# dlp_vco_dualosc_v1_1_pnl.net
KiCad netlist of a schematic drawn in EAGLE
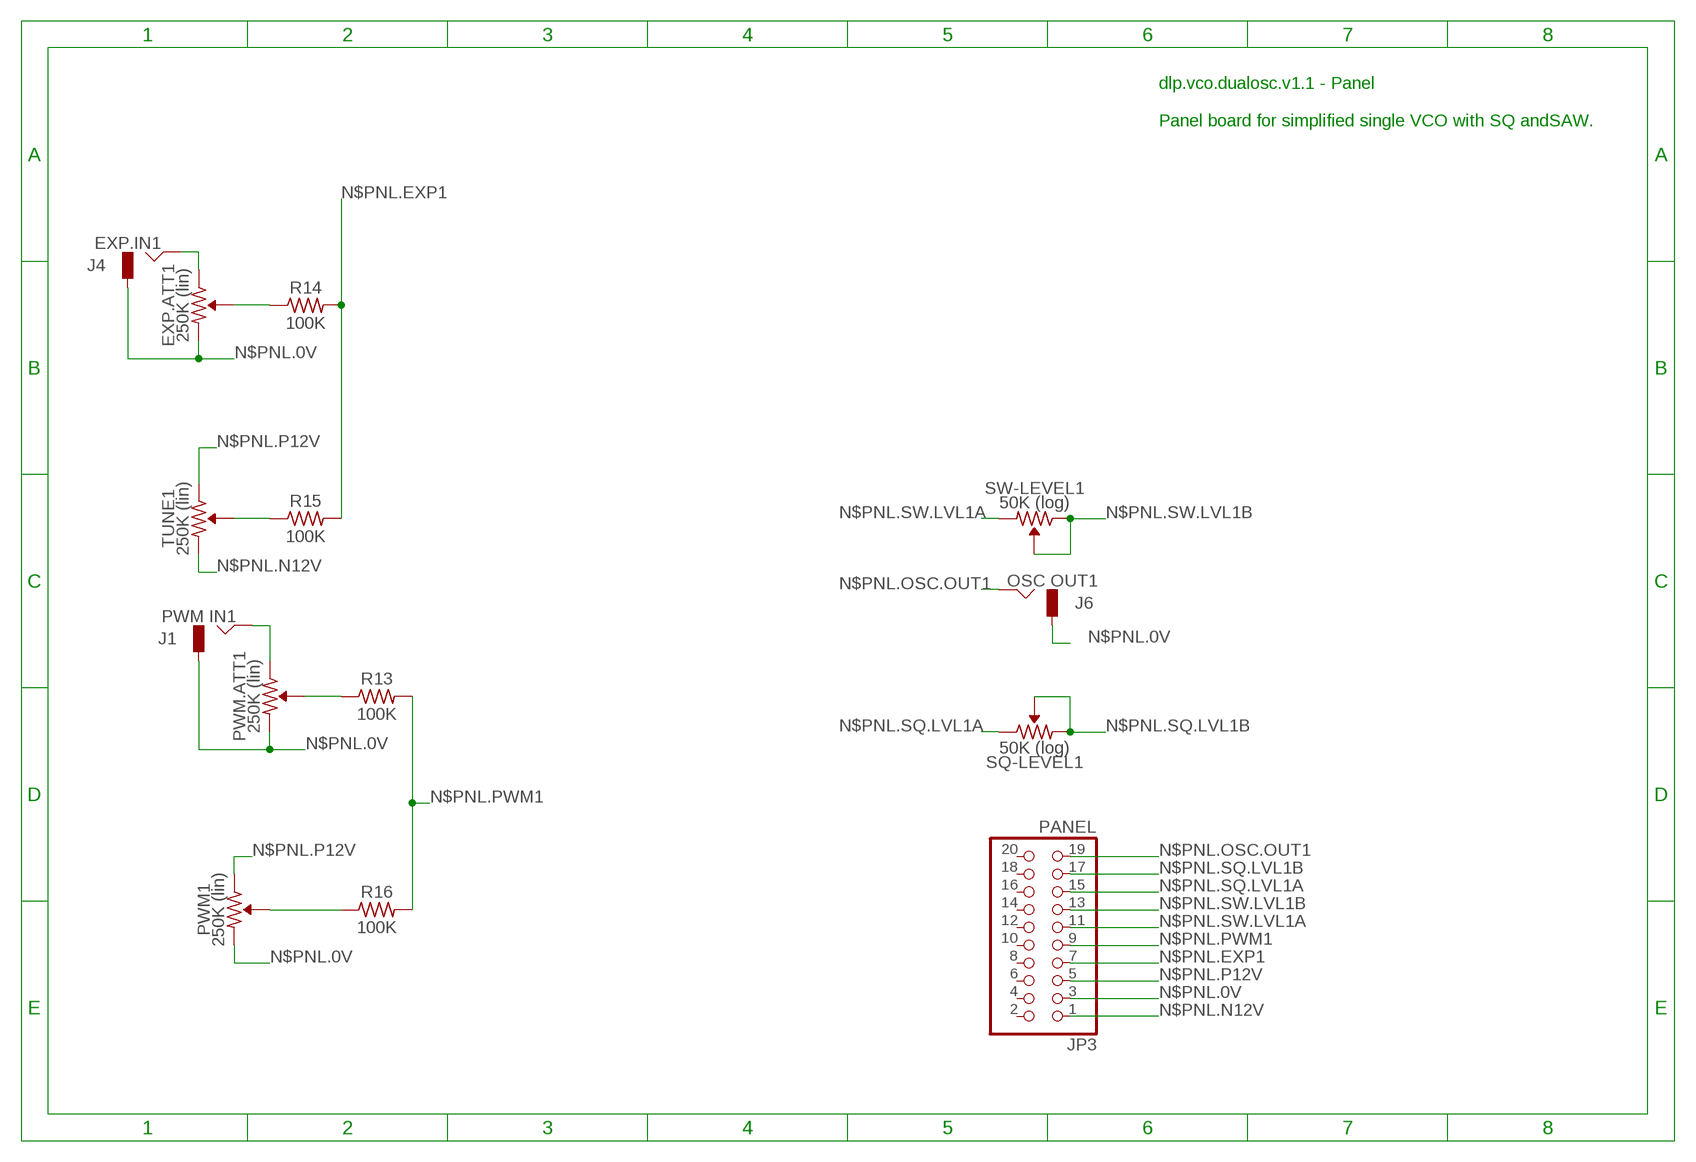
[diagram p0: schematic, sheet 1]

(export (version "E")
  (design (tool "Eeschema 10.0.6"))
  (components
    (comp (ref "EXP.ATT1")
      (value "250K (lin)")
      (footprint "eagle-import:R-VAR")
      (libsource (lib "eagle-import") (part "R-VAR"))
    )
    (comp (ref "J1")
      (value "PWM IN1")
      (footprint "eagle-import:JACK-M")
      (libsource (lib "eagle-import") (part "JACK-M"))
    )
    (comp (ref "J4")
      (value "EXP.IN1")
      (footprint "eagle-import:JACK-M")
      (libsource (lib "eagle-import") (part "JACK-M"))
    )
    (comp (ref "J6")
      (value "OSC OUT1")
      (footprint "eagle-import:JACK-M")
      (libsource (lib "eagle-import") (part "JACK-M"))
    )
    (comp (ref "JP3")
      (value "PANEL")
      (footprint "eagle-import:2X10")
      (libsource (lib "eagle-import") (part "PINHD-2X10"))
    )
    (comp (ref "PWM.ATT1")
      (value "250K (lin)")
      (footprint "eagle-import:R-VAR")
      (libsource (lib "eagle-import") (part "R-VAR"))
    )
    (comp (ref "PWM1")
      (value "250K (lin)")
      (footprint "eagle-import:R-VAR")
      (libsource (lib "eagle-import") (part "R-VAR"))
    )
    (comp (ref "R13")
      (value "100K")
      (footprint "eagle-import:0309_10")
      (libsource (lib "eagle-import") (part "R0309/10"))
    )
    (comp (ref "R14")
      (value "100K")
      (footprint "eagle-import:0309_10")
      (libsource (lib "eagle-import") (part "R0309/10"))
    )
    (comp (ref "R15")
      (value "100K")
      (footprint "eagle-import:0309_10")
      (libsource (lib "eagle-import") (part "R0309/10"))
    )
    (comp (ref "R16")
      (value "100K")
      (footprint "eagle-import:0309_10")
      (libsource (lib "eagle-import") (part "R0309/10"))
    )
    (comp (ref "SQ-LEVEL1")
      (value "50K (log)")
      (footprint "eagle-import:R-VAR")
      (libsource (lib "eagle-import") (part "R-VAR"))
    )
    (comp (ref "SW-LEVEL1")
      (value "50K (log)")
      (footprint "eagle-import:R-VAR")
      (libsource (lib "eagle-import") (part "R-VAR"))
    )
    (comp (ref "TUNE1")
      (value "250K (lin)")
      (footprint "eagle-import:R-VAR")
      (libsource (lib "eagle-import") (part "R-VAR"))
    )
  )
  (nets
    (net (code "1") (name "/N$PNL.0V") (class "Default")
      (node (ref "EXP.ATT1") (pin "R2") (pinfunction "2_R2") (pintype "passive"))
      (node (ref "J1") (pin "GND") (pinfunction "GND_GND") (pintype "bidirectional"))
      (node (ref "J4") (pin "GND") (pinfunction "GND_GND") (pintype "bidirectional"))
      (node (ref "J6") (pin "GND") (pinfunction "GND_GND") (pintype "bidirectional"))
      (node (ref "JP3") (pin "3") (pinfunction "3_3") (pintype "passive"))
      (node (ref "PWM.ATT1") (pin "R2") (pinfunction "2_R2") (pintype "passive"))
      (node (ref "PWM1") (pin "R2") (pinfunction "2_R2") (pintype "passive"))
    )
    (net (code "2") (name "/N$PNL.EXP1") (class "Default")
      (node (ref "JP3") (pin "7") (pinfunction "7_7") (pintype "passive"))
      (node (ref "R14") (pin "2") (pinfunction "2_2") (pintype "passive"))
      (node (ref "R15") (pin "2") (pinfunction "2_2") (pintype "passive"))
    )
    (net (code "3") (name "/N$PNL.N12V") (class "Default")
      (node (ref "JP3") (pin "1") (pinfunction "1_1") (pintype "passive"))
      (node (ref "TUNE1") (pin "R2") (pinfunction "2_R2") (pintype "passive"))
    )
    (net (code "4") (name "/N$PNL.OSC.OUT1") (class "Default")
      (node (ref "J6") (pin "HOT") (pinfunction "HOT_HOT") (pintype "bidirectional"))
      (node (ref "JP3") (pin "19") (pinfunction "19_19") (pintype "passive"))
    )
    (net (code "5") (name "/N$PNL.P12V") (class "Default")
      (node (ref "JP3") (pin "5") (pinfunction "5_5") (pintype "passive"))
      (node (ref "PWM1") (pin "R1") (pinfunction "1_R1") (pintype "passive"))
      (node (ref "TUNE1") (pin "R1") (pinfunction "1_R1") (pintype "passive"))
    )
    (net (code "6") (name "/N$PNL.PWM1") (class "Default")
      (node (ref "JP3") (pin "9") (pinfunction "9_9") (pintype "passive"))
      (node (ref "R13") (pin "2") (pinfunction "2_2") (pintype "passive"))
      (node (ref "R16") (pin "2") (pinfunction "2_2") (pintype "passive"))
    )
    (net (code "7") (name "/N$PNL.SQ.LVL1A") (class "Default")
      (node (ref "JP3") (pin "15") (pinfunction "15_15") (pintype "passive"))
      (node (ref "SQ-LEVEL1") (pin "R1") (pinfunction "1_R1") (pintype "passive"))
    )
    (net (code "8") (name "/N$PNL.SQ.LVL1B") (class "Default")
      (node (ref "JP3") (pin "17") (pinfunction "17_17") (pintype "passive"))
      (node (ref "SQ-LEVEL1") (pin "R2") (pinfunction "2_R2") (pintype "passive"))
      (node (ref "SQ-LEVEL1") (pin "VAR") (pinfunction "P$1_VAR") (pintype "passive"))
    )
    (net (code "9") (name "/N$PNL.SW.LVL1A") (class "Default")
      (node (ref "JP3") (pin "11") (pinfunction "11_11") (pintype "passive"))
      (node (ref "SW-LEVEL1") (pin "R2") (pinfunction "2_R2") (pintype "passive"))
    )
    (net (code "10") (name "/N$PNL.SW.LVL1B") (class "Default")
      (node (ref "JP3") (pin "13") (pinfunction "13_13") (pintype "passive"))
      (node (ref "SW-LEVEL1") (pin "R1") (pinfunction "1_R1") (pintype "passive"))
      (node (ref "SW-LEVEL1") (pin "VAR") (pinfunction "P$1_VAR") (pintype "passive"))
    )
    (net (code "11") (name "Net-(EXP.ATT1-1)") (class "Default")
      (node (ref "EXP.ATT1") (pin "R1") (pinfunction "1_R1") (pintype "passive"))
      (node (ref "J4") (pin "HOT") (pinfunction "HOT_HOT") (pintype "bidirectional"))
    )
    (net (code "12") (name "Net-(EXP.ATT1-P$1)") (class "Default")
      (node (ref "EXP.ATT1") (pin "VAR") (pinfunction "P$1_VAR") (pintype "passive"))
      (node (ref "R14") (pin "1") (pinfunction "1_1") (pintype "passive"))
    )
    (net (code "13") (name "Net-(PWM.ATT1-1)") (class "Default")
      (node (ref "J1") (pin "HOT") (pinfunction "HOT_HOT") (pintype "bidirectional"))
      (node (ref "PWM.ATT1") (pin "R1") (pinfunction "1_R1") (pintype "passive"))
    )
    (net (code "14") (name "Net-(PWM.ATT1-P$1)") (class "Default")
      (node (ref "PWM.ATT1") (pin "VAR") (pinfunction "P$1_VAR") (pintype "passive"))
      (node (ref "R13") (pin "1") (pinfunction "1_1") (pintype "passive"))
    )
    (net (code "15") (name "Net-(PWM1-P$1)") (class "Default")
      (node (ref "PWM1") (pin "VAR") (pinfunction "P$1_VAR") (pintype "passive"))
      (node (ref "R16") (pin "1") (pinfunction "1_1") (pintype "passive"))
    )
    (net (code "16") (name "Net-(TUNE1-P$1)") (class "Default")
      (node (ref "R15") (pin "1") (pinfunction "1_1") (pintype "passive"))
      (node (ref "TUNE1") (pin "VAR") (pinfunction "P$1_VAR") (pintype "passive"))
    )
    (net (code "17") (name "unconnected-(JP3-Pad2)") (class "Default")
      (node (ref "JP3") (pin "2") (pinfunction "2_2") (pintype "passive"))
    )
    (net (code "18") (name "unconnected-(JP3-Pad4)") (class "Default")
      (node (ref "JP3") (pin "4") (pinfunction "4_4") (pintype "passive"))
    )
    (net (code "19") (name "unconnected-(JP3-Pad6)") (class "Default")
      (node (ref "JP3") (pin "6") (pinfunction "6_6") (pintype "passive"))
    )
    (net (code "20") (name "unconnected-(JP3-Pad8)") (class "Default")
      (node (ref "JP3") (pin "8") (pinfunction "8_8") (pintype "passive"))
    )
    (net (code "21") (name "unconnected-(JP3-Pad10)") (class "Default")
      (node (ref "JP3") (pin "10") (pinfunction "10_10") (pintype "passive"))
    )
    (net (code "22") (name "unconnected-(JP3-Pad12)") (class "Default")
      (node (ref "JP3") (pin "12") (pinfunction "12_12") (pintype "passive"))
    )
    (net (code "23") (name "unconnected-(JP3-Pad14)") (class "Default")
      (node (ref "JP3") (pin "14") (pinfunction "14_14") (pintype "passive"))
    )
    (net (code "24") (name "unconnected-(JP3-Pad16)") (class "Default")
      (node (ref "JP3") (pin "16") (pinfunction "16_16") (pintype "passive"))
    )
    (net (code "25") (name "unconnected-(JP3-Pad18)") (class "Default")
      (node (ref "JP3") (pin "18") (pinfunction "18_18") (pintype "passive"))
    )
    (net (code "26") (name "unconnected-(JP3-Pad20)") (class "Default")
      (node (ref "JP3") (pin "20") (pinfunction "20_20") (pintype "passive"))
    )
  )
)
